# BLDC_driver_sensorless_power.net
KiCad netlist of a schematic drawn in Altium Designer
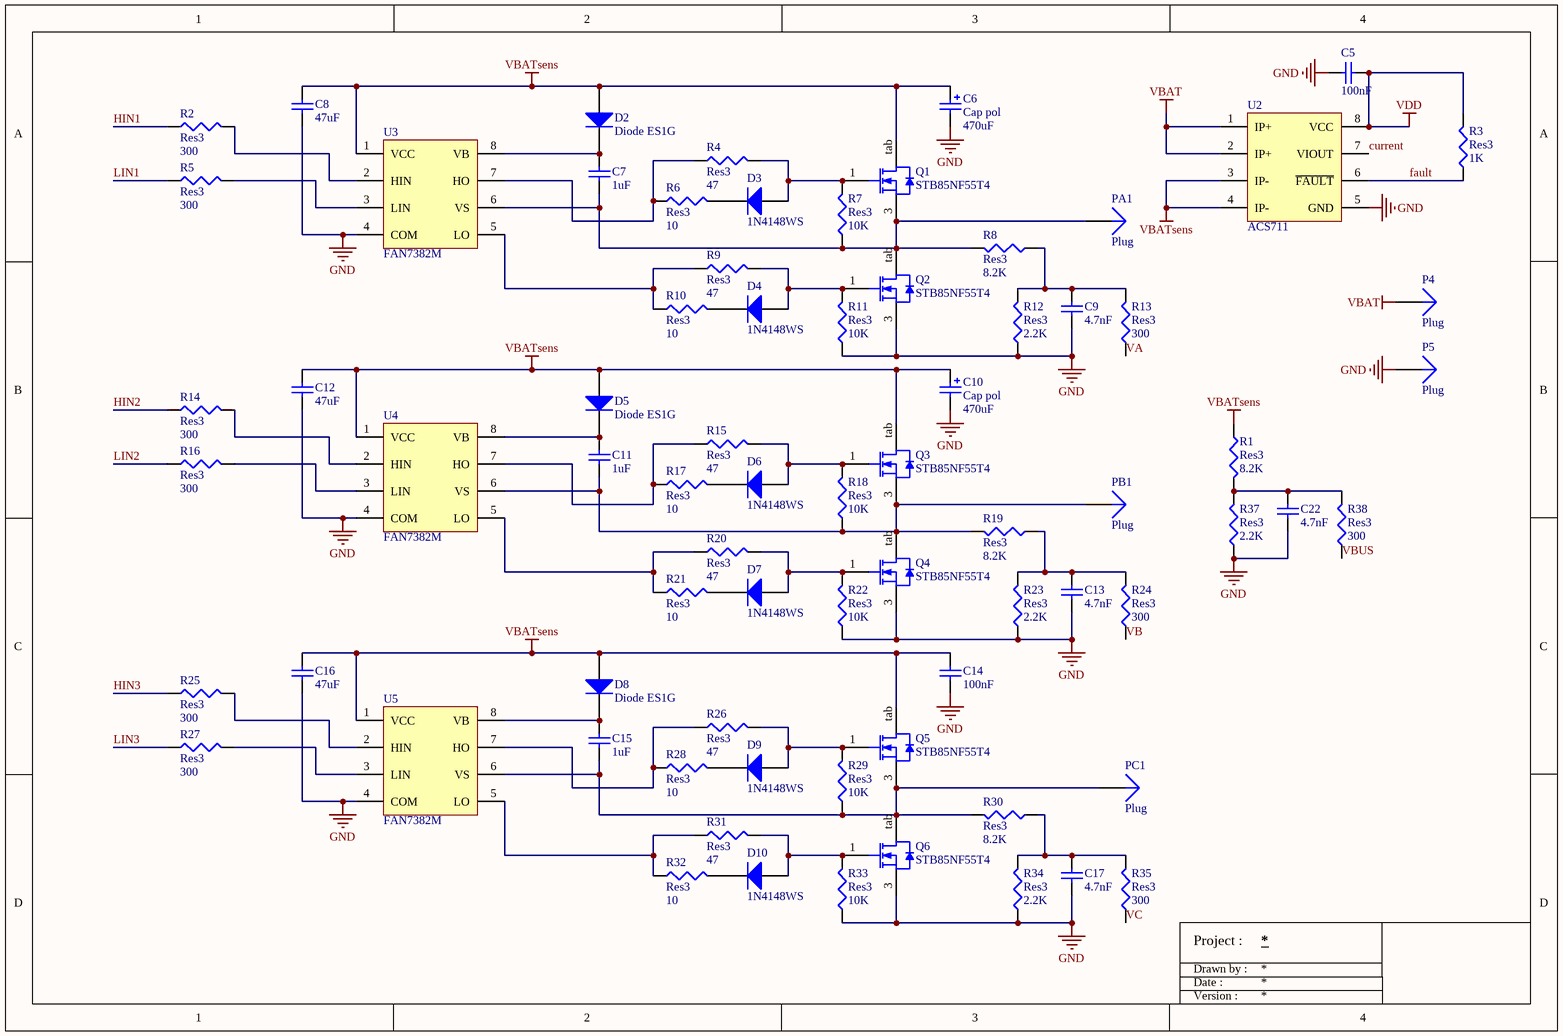
[diagram p0: BLDC_driver_sensorless_power.SchDoc]

(export (version "E")
  (design (tool "Eeschema 10.0.6"))
  (components
    (comp (ref "C5")
      (value "100nF")
      (footprint "1206 capacitor")
      (description "SMD capacitor")
      (fields (field (name "Comment") "Cap SMD"))
      (libsource (lib "Miscellaneous Devices") (part "Cap SMD"))
    )
    (comp (ref "C6")
      (value "Cap pol")
      (footprint "Cap elec 10x16-5 Surface Mount")
      (description "Capa pol through hole")
      (fields (field (name "ALTIUM_VALUE") "470uF"))
      (libsource (lib "Miscellaneous Devices 2") (part "Cap pol"))
    )
    (comp (ref "C7")
      (value "1uF")
      (footprint "1206 capacitor")
      (description "SMD capacitor")
      (fields (field (name "Comment") "Cap SMD"))
      (libsource (lib "Miscellaneous Devices") (part "Cap SMD"))
    )
    (comp (ref "C8")
      (value "47uF")
      (footprint "1206 capacitor")
      (description "SMD capacitor")
      (fields (field (name "Comment") "Cap SMD"))
      (libsource (lib "Miscellaneous Devices") (part "Cap SMD"))
    )
    (comp (ref "C9")
      (value "4.7nF")
      (footprint "1206 capacitor")
      (description "SMD capacitor")
      (fields (field (name "Comment") "Cap SMD"))
      (libsource (lib "Miscellaneous Devices") (part "Cap SMD"))
    )
    (comp (ref "C10")
      (value "Cap pol")
      (footprint "Cap elec 10x16-5 Surface Mount")
      (description "Capa pol through hole")
      (fields (field (name "ALTIUM_VALUE") "470uF"))
      (libsource (lib "Miscellaneous Devices 2") (part "Cap pol"))
    )
    (comp (ref "C11")
      (value "1uF")
      (footprint "1206 capacitor")
      (description "SMD capacitor")
      (fields (field (name "Comment") "Cap SMD"))
      (libsource (lib "Miscellaneous Devices") (part "Cap SMD"))
    )
    (comp (ref "C12")
      (value "47uF")
      (footprint "1206 capacitor")
      (description "SMD capacitor")
      (fields (field (name "Comment") "Cap SMD"))
      (libsource (lib "Miscellaneous Devices") (part "Cap SMD"))
    )
    (comp (ref "C13")
      (value "4.7nF")
      (footprint "1206 capacitor")
      (description "SMD capacitor")
      (fields (field (name "Comment") "Cap SMD"))
      (libsource (lib "Miscellaneous Devices") (part "Cap SMD"))
    )
    (comp (ref "C14")
      (value "100nF")
      (footprint "1206 capacitor")
      (description "SMD capacitor")
      (fields (field (name "Comment") "Cap SMD"))
      (libsource (lib "Miscellaneous Devices") (part "Cap SMD"))
    )
    (comp (ref "C15")
      (value "1uF")
      (footprint "1206 capacitor")
      (description "SMD capacitor")
      (fields (field (name "Comment") "Cap SMD"))
      (libsource (lib "Miscellaneous Devices") (part "Cap SMD"))
    )
    (comp (ref "C16")
      (value "47uF")
      (footprint "1206 capacitor")
      (description "SMD capacitor")
      (fields (field (name "Comment") "Cap SMD"))
      (libsource (lib "Miscellaneous Devices") (part "Cap SMD"))
    )
    (comp (ref "C17")
      (value "4.7nF")
      (footprint "1206 capacitor")
      (description "SMD capacitor")
      (fields (field (name "Comment") "Cap SMD"))
      (libsource (lib "Miscellaneous Devices") (part "Cap SMD"))
    )
    (comp (ref "C22")
      (value "4.7nF")
      (footprint "1206 capacitor")
      (description "SMD capacitor")
      (fields (field (name "Comment") "Cap SMD"))
      (libsource (lib "Miscellaneous Devices") (part "Cap SMD"))
    )
    (comp (ref "D2")
      (value "Diode ES1G")
      (footprint "DO-214AC")
      (description "1.0A SURFACE MOUNT SUPER-FAST RECTIFIER")
      (libsource (lib "Miscellaneous Devices 2") (part "Diode ES1G"))
    )
    (comp (ref "D3")
      (value "1N4148WS")
      (footprint "SOD323")
      (description "Diode commutation")
      (libsource (lib "Miscellaneous Devices 2") (part "1N4148WS"))
    )
    (comp (ref "D4")
      (value "1N4148WS")
      (footprint "SOD323")
      (description "Diode commutation")
      (libsource (lib "Miscellaneous Devices 2") (part "1N4148WS"))
    )
    (comp (ref "D5")
      (value "Diode ES1G")
      (footprint "DO-214AC")
      (description "1.0A SURFACE MOUNT SUPER-FAST RECTIFIER")
      (libsource (lib "Miscellaneous Devices 2") (part "Diode ES1G"))
    )
    (comp (ref "D6")
      (value "1N4148WS")
      (footprint "SOD323")
      (description "Diode commutation")
      (libsource (lib "Miscellaneous Devices 2") (part "1N4148WS"))
    )
    (comp (ref "D7")
      (value "1N4148WS")
      (footprint "SOD323")
      (description "Diode commutation")
      (libsource (lib "Miscellaneous Devices 2") (part "1N4148WS"))
    )
    (comp (ref "D8")
      (value "Diode ES1G")
      (footprint "DO-214AC")
      (description "1.0A SURFACE MOUNT SUPER-FAST RECTIFIER")
      (libsource (lib "Miscellaneous Devices 2") (part "Diode ES1G"))
    )
    (comp (ref "D9")
      (value "1N4148WS")
      (footprint "SOD323")
      (description "Diode commutation")
      (libsource (lib "Miscellaneous Devices 2") (part "1N4148WS"))
    )
    (comp (ref "D10")
      (value "1N4148WS")
      (footprint "SOD323")
      (description "Diode commutation")
      (libsource (lib "Miscellaneous Devices 2") (part "1N4148WS"))
    )
    (comp (ref "P4")
      (value "Plug")
      (footprint "PIN1")
      (fields (field (name "PUBLISHER") "Altium Limited"))
      (libsource (lib "Miscellaneous Connectors") (part "Plug"))
    )
    (comp (ref "P5")
      (value "Plug")
      (footprint "PIN1")
      (fields (field (name "PUBLISHER") "Altium Limited"))
      (libsource (lib "Miscellaneous Connectors") (part "Plug"))
    )
    (comp (ref "PA1")
      (value "Plug")
      (footprint "PIN1")
      (fields (field (name "PUBLISHER") "Altium Limited"))
      (libsource (lib "Miscellaneous Connectors") (part "Plug"))
    )
    (comp (ref "PB1")
      (value "Plug")
      (footprint "PIN1")
      (fields (field (name "PUBLISHER") "Altium Limited"))
      (libsource (lib "Miscellaneous Connectors") (part "Plug"))
    )
    (comp (ref "PC1")
      (value "Plug")
      (footprint "PIN1")
      (fields (field (name "PUBLISHER") "Altium Limited"))
      (libsource (lib "Miscellaneous Connectors") (part "Plug"))
    )
    (comp (ref "Q1")
      (value "STB85NF55T4")
      (footprint "TO-263-2")
      (description "MOSFET Canal-N, 80A 55V")
      (libsource (lib "Miscellaneous Devices 2") (part "STB85NF55T4"))
    )
    (comp (ref "Q2")
      (value "STB85NF55T4")
      (footprint "TO-263-2")
      (description "MOSFET Canal-N, 80A 55V")
      (libsource (lib "Miscellaneous Devices 2") (part "STB85NF55T4"))
    )
    (comp (ref "Q3")
      (value "STB85NF55T4")
      (footprint "TO-263-2")
      (description "MOSFET Canal-N, 80A 55V")
      (libsource (lib "Miscellaneous Devices 2") (part "STB85NF55T4"))
    )
    (comp (ref "Q4")
      (value "STB85NF55T4")
      (footprint "TO-263-2")
      (description "MOSFET Canal-N, 80A 55V")
      (libsource (lib "Miscellaneous Devices 2") (part "STB85NF55T4"))
    )
    (comp (ref "Q5")
      (value "STB85NF55T4")
      (footprint "TO-263-2")
      (description "MOSFET Canal-N, 80A 55V")
      (libsource (lib "Miscellaneous Devices 2") (part "STB85NF55T4"))
    )
    (comp (ref "Q6")
      (value "STB85NF55T4")
      (footprint "TO-263-2")
      (description "MOSFET Canal-N, 80A 55V")
      (libsource (lib "Miscellaneous Devices 2") (part "STB85NF55T4"))
    )
    (comp (ref "R1")
      (value "Res3")
      (footprint "1206 resistor")
      (description "Resistor")
      (fields (field (name "ALTIUM_VALUE") "8.2K") (field (name "PUBLISHER") "Altium Limited"))
      (libsource (lib "Miscellaneous Devices") (part "Res3"))
    )
    (comp (ref "R2")
      (value "Res3")
      (footprint "1206 resistor")
      (description "Resistor")
      (fields (field (name "ALTIUM_VALUE") "300") (field (name "PUBLISHER") "Altium Limited"))
      (libsource (lib "Miscellaneous Devices") (part "Res3"))
    )
    (comp (ref "R3")
      (value "Res3")
      (footprint "1206 resistor")
      (description "Resistor")
      (fields (field (name "ALTIUM_VALUE") "1K") (field (name "PUBLISHER") "Altium Limited"))
      (libsource (lib "Miscellaneous Devices") (part "Res3"))
    )
    (comp (ref "R4")
      (value "Res3")
      (footprint "1206 resistor")
      (description "Resistor")
      (fields (field (name "ALTIUM_VALUE") "47") (field (name "PUBLISHER") "Altium Limited"))
      (libsource (lib "Miscellaneous Devices") (part "Res3"))
    )
    (comp (ref "R5")
      (value "Res3")
      (footprint "1206 resistor")
      (description "Resistor")
      (fields (field (name "ALTIUM_VALUE") "300") (field (name "PUBLISHER") "Altium Limited"))
      (libsource (lib "Miscellaneous Devices") (part "Res3"))
    )
    (comp (ref "R6")
      (value "Res3")
      (footprint "1206 resistor")
      (description "Resistor")
      (fields (field (name "ALTIUM_VALUE") "10") (field (name "PUBLISHER") "Altium Limited"))
      (libsource (lib "Miscellaneous Devices") (part "Res3"))
    )
    (comp (ref "R7")
      (value "Res3")
      (footprint "1206 resistor")
      (description "Resistor")
      (fields (field (name "ALTIUM_VALUE") "10K") (field (name "PUBLISHER") "Altium Limited"))
      (libsource (lib "Miscellaneous Devices") (part "Res3"))
    )
    (comp (ref "R8")
      (value "Res3")
      (footprint "1206 resistor")
      (description "Resistor")
      (fields (field (name "ALTIUM_VALUE") "8.2K") (field (name "PUBLISHER") "Altium Limited"))
      (libsource (lib "Miscellaneous Devices") (part "Res3"))
    )
    (comp (ref "R9")
      (value "Res3")
      (footprint "1206 resistor")
      (description "Resistor")
      (fields (field (name "ALTIUM_VALUE") "47") (field (name "PUBLISHER") "Altium Limited"))
      (libsource (lib "Miscellaneous Devices") (part "Res3"))
    )
    (comp (ref "R10")
      (value "Res3")
      (footprint "1206 resistor")
      (description "Resistor")
      (fields (field (name "ALTIUM_VALUE") "10") (field (name "PUBLISHER") "Altium Limited"))
      (libsource (lib "Miscellaneous Devices") (part "Res3"))
    )
    (comp (ref "R11")
      (value "Res3")
      (footprint "1206 resistor")
      (description "Resistor")
      (fields (field (name "ALTIUM_VALUE") "10K") (field (name "PUBLISHER") "Altium Limited"))
      (libsource (lib "Miscellaneous Devices") (part "Res3"))
    )
    (comp (ref "R12")
      (value "Res3")
      (footprint "1206 resistor")
      (description "Resistor")
      (fields (field (name "ALTIUM_VALUE") "2.2K") (field (name "PUBLISHER") "Altium Limited"))
      (libsource (lib "Miscellaneous Devices") (part "Res3"))
    )
    (comp (ref "R13")
      (value "Res3")
      (footprint "1206 resistor")
      (description "Resistor")
      (fields (field (name "ALTIUM_VALUE") "300") (field (name "PUBLISHER") "Altium Limited"))
      (libsource (lib "Miscellaneous Devices") (part "Res3"))
    )
    (comp (ref "R14")
      (value "Res3")
      (footprint "1206 resistor")
      (description "Resistor")
      (fields (field (name "ALTIUM_VALUE") "300") (field (name "PUBLISHER") "Altium Limited"))
      (libsource (lib "Miscellaneous Devices") (part "Res3"))
    )
    (comp (ref "R15")
      (value "Res3")
      (footprint "1206 resistor")
      (description "Resistor")
      (fields (field (name "ALTIUM_VALUE") "47") (field (name "PUBLISHER") "Altium Limited"))
      (libsource (lib "Miscellaneous Devices") (part "Res3"))
    )
    (comp (ref "R16")
      (value "Res3")
      (footprint "1206 resistor")
      (description "Resistor")
      (fields (field (name "ALTIUM_VALUE") "300") (field (name "PUBLISHER") "Altium Limited"))
      (libsource (lib "Miscellaneous Devices") (part "Res3"))
    )
    (comp (ref "R17")
      (value "Res3")
      (footprint "1206 resistor")
      (description "Resistor")
      (fields (field (name "ALTIUM_VALUE") "10") (field (name "PUBLISHER") "Altium Limited"))
      (libsource (lib "Miscellaneous Devices") (part "Res3"))
    )
    (comp (ref "R18")
      (value "Res3")
      (footprint "1206 resistor")
      (description "Resistor")
      (fields (field (name "ALTIUM_VALUE") "10K") (field (name "PUBLISHER") "Altium Limited"))
      (libsource (lib "Miscellaneous Devices") (part "Res3"))
    )
    (comp (ref "R19")
      (value "Res3")
      (footprint "1206 resistor")
      (description "Resistor")
      (fields (field (name "ALTIUM_VALUE") "8.2K") (field (name "PUBLISHER") "Altium Limited"))
      (libsource (lib "Miscellaneous Devices") (part "Res3"))
    )
    (comp (ref "R20")
      (value "Res3")
      (footprint "1206 resistor")
      (description "Resistor")
      (fields (field (name "ALTIUM_VALUE") "47") (field (name "PUBLISHER") "Altium Limited"))
      (libsource (lib "Miscellaneous Devices") (part "Res3"))
    )
    (comp (ref "R21")
      (value "Res3")
      (footprint "1206 resistor")
      (description "Resistor")
      (fields (field (name "ALTIUM_VALUE") "10") (field (name "PUBLISHER") "Altium Limited"))
      (libsource (lib "Miscellaneous Devices") (part "Res3"))
    )
    (comp (ref "R22")
      (value "Res3")
      (footprint "1206 resistor")
      (description "Resistor")
      (fields (field (name "ALTIUM_VALUE") "10K") (field (name "PUBLISHER") "Altium Limited"))
      (libsource (lib "Miscellaneous Devices") (part "Res3"))
    )
    (comp (ref "R23")
      (value "Res3")
      (footprint "1206 resistor")
      (description "Resistor")
      (fields (field (name "ALTIUM_VALUE") "2.2K") (field (name "PUBLISHER") "Altium Limited"))
      (libsource (lib "Miscellaneous Devices") (part "Res3"))
    )
    (comp (ref "R24")
      (value "Res3")
      (footprint "1206 resistor")
      (description "Resistor")
      (fields (field (name "ALTIUM_VALUE") "300") (field (name "PUBLISHER") "Altium Limited"))
      (libsource (lib "Miscellaneous Devices") (part "Res3"))
    )
    (comp (ref "R25")
      (value "Res3")
      (footprint "1206 resistor")
      (description "Resistor")
      (fields (field (name "ALTIUM_VALUE") "300") (field (name "PUBLISHER") "Altium Limited"))
      (libsource (lib "Miscellaneous Devices") (part "Res3"))
    )
    (comp (ref "R26")
      (value "Res3")
      (footprint "1206 resistor")
      (description "Resistor")
      (fields (field (name "ALTIUM_VALUE") "47") (field (name "PUBLISHER") "Altium Limited"))
      (libsource (lib "Miscellaneous Devices") (part "Res3"))
    )
    (comp (ref "R27")
      (value "Res3")
      (footprint "1206 resistor")
      (description "Resistor")
      (fields (field (name "ALTIUM_VALUE") "300") (field (name "PUBLISHER") "Altium Limited"))
      (libsource (lib "Miscellaneous Devices") (part "Res3"))
    )
    (comp (ref "R28")
      (value "Res3")
      (footprint "1206 resistor")
      (description "Resistor")
      (fields (field (name "ALTIUM_VALUE") "10") (field (name "PUBLISHER") "Altium Limited"))
      (libsource (lib "Miscellaneous Devices") (part "Res3"))
    )
    (comp (ref "R29")
      (value "Res3")
      (footprint "1206 resistor")
      (description "Resistor")
      (fields (field (name "ALTIUM_VALUE") "10K") (field (name "PUBLISHER") "Altium Limited"))
      (libsource (lib "Miscellaneous Devices") (part "Res3"))
    )
    (comp (ref "R30")
      (value "Res3")
      (footprint "1206 resistor")
      (description "Resistor")
      (fields (field (name "ALTIUM_VALUE") "8.2K") (field (name "PUBLISHER") "Altium Limited"))
      (libsource (lib "Miscellaneous Devices") (part "Res3"))
    )
    (comp (ref "R31")
      (value "Res3")
      (footprint "1206 resistor")
      (description "Resistor")
      (fields (field (name "ALTIUM_VALUE") "47") (field (name "PUBLISHER") "Altium Limited"))
      (libsource (lib "Miscellaneous Devices") (part "Res3"))
    )
    (comp (ref "R32")
      (value "Res3")
      (footprint "1206 resistor")
      (description "Resistor")
      (fields (field (name "ALTIUM_VALUE") "10") (field (name "PUBLISHER") "Altium Limited"))
      (libsource (lib "Miscellaneous Devices") (part "Res3"))
    )
    (comp (ref "R33")
      (value "Res3")
      (footprint "1206 resistor")
      (description "Resistor")
      (fields (field (name "ALTIUM_VALUE") "10K") (field (name "PUBLISHER") "Altium Limited"))
      (libsource (lib "Miscellaneous Devices") (part "Res3"))
    )
    (comp (ref "R34")
      (value "Res3")
      (footprint "1206 resistor")
      (description "Resistor")
      (fields (field (name "ALTIUM_VALUE") "2.2K") (field (name "PUBLISHER") "Altium Limited"))
      (libsource (lib "Miscellaneous Devices") (part "Res3"))
    )
    (comp (ref "R35")
      (value "Res3")
      (footprint "1206 resistor")
      (description "Resistor")
      (fields (field (name "ALTIUM_VALUE") "300") (field (name "PUBLISHER") "Altium Limited"))
      (libsource (lib "Miscellaneous Devices") (part "Res3"))
    )
    (comp (ref "R37")
      (value "Res3")
      (footprint "1206 resistor")
      (description "Resistor")
      (fields (field (name "ALTIUM_VALUE") "2.2K") (field (name "PUBLISHER") "Altium Limited"))
      (libsource (lib "Miscellaneous Devices") (part "Res3"))
    )
    (comp (ref "R38")
      (value "Res3")
      (footprint "1206 resistor")
      (description "Resistor")
      (fields (field (name "ALTIUM_VALUE") "300") (field (name "PUBLISHER") "Altium Limited"))
      (libsource (lib "Miscellaneous Devices") (part "Res3"))
    )
    (comp (ref "U2")
      (value "ACS711")
      (footprint "SOIC8")
      (description "+/-12A HALL EFFECT CURRENT SENSOR")
      (libsource (lib "Miscellaneous Devices 2") (part "ACS711"))
    )
    (comp (ref "U3")
      (value "FAN7382M")
      (footprint "SOIC8")
      (description "High and Low Side Gate Driver")
      (libsource (lib "Miscellaneous Devices 2") (part "FAN7382M"))
    )
    (comp (ref "U4")
      (value "FAN7382M")
      (footprint "SOIC8")
      (description "High and Low Side Gate Driver")
      (libsource (lib "Miscellaneous Devices 2") (part "FAN7382M"))
    )
    (comp (ref "U5")
      (value "FAN7382M")
      (footprint "SOIC8")
      (description "High and Low Side Gate Driver")
      (libsource (lib "Miscellaneous Devices 2") (part "FAN7382M"))
    )
  )
  (nets
    (net (code "1") (name "/HIN1") (class "Default")
      (node (ref "R2") (pin "1") (pinfunction "1_1") (pintype "passive"))
    )
    (net (code "2") (name "/HIN2") (class "Default")
      (node (ref "R14") (pin "1") (pinfunction "1_1") (pintype "passive"))
    )
    (net (code "3") (name "/HIN3") (class "Default")
      (node (ref "R25") (pin "1") (pinfunction "1_1") (pintype "passive"))
    )
    (net (code "4") (name "/LIN1") (class "Default")
      (node (ref "R5") (pin "1") (pinfunction "1_1") (pintype "passive"))
    )
    (net (code "5") (name "/LIN2") (class "Default")
      (node (ref "R16") (pin "1") (pinfunction "1_1") (pintype "passive"))
    )
    (net (code "6") (name "/LIN3") (class "Default")
      (node (ref "R27") (pin "1") (pinfunction "1_1") (pintype "passive"))
    )
    (net (code "7") (name "/VA") (class "Default")
      (node (ref "R13") (pin "1") (pinfunction "1_1") (pintype "passive"))
    )
    (net (code "8") (name "/VB") (class "Default")
      (node (ref "R24") (pin "1") (pinfunction "1_1") (pintype "passive"))
    )
    (net (code "9") (name "/VBUS") (class "Default")
      (node (ref "R38") (pin "1") (pinfunction "1_1") (pintype "passive"))
    )
    (net (code "10") (name "/VC") (class "Default")
      (node (ref "R35") (pin "1") (pinfunction "1_1") (pintype "passive"))
    )
    (net (code "11") (name "/current") (class "Default")
      (node (ref "U2") (pin "7") (pinfunction "VIOUT_7") (pintype "passive"))
    )
    (net (code "12") (name "/fault") (class "Default")
      (node (ref "R3") (pin "1") (pinfunction "1_1") (pintype "passive"))
      (node (ref "U2") (pin "6") (pinfunction "~{FAULT}_6") (pintype "passive"))
    )
    (net (code "13") (name "GND") (class "Default")
      (node (ref "C10") (pin "2") (pinfunction "2_2") (pintype "passive"))
      (node (ref "C12") (pin "1") (pinfunction "1_1") (pintype "passive"))
      (node (ref "C13") (pin "2") (pinfunction "2_2") (pintype "passive"))
      (node (ref "C14") (pin "2") (pinfunction "2_2") (pintype "passive"))
      (node (ref "C16") (pin "1") (pinfunction "1_1") (pintype "passive"))
      (node (ref "C17") (pin "2") (pinfunction "2_2") (pintype "passive"))
      (node (ref "C22") (pin "2") (pinfunction "2_2") (pintype "passive"))
      (node (ref "C5") (pin "2") (pinfunction "2_2") (pintype "passive"))
      (node (ref "C6") (pin "2") (pinfunction "2_2") (pintype "passive"))
      (node (ref "C8") (pin "1") (pinfunction "1_1") (pintype "passive"))
      (node (ref "C9") (pin "2") (pinfunction "2_2") (pintype "passive"))
      (node (ref "P5") (pin "1") (pinfunction "1_1") (pintype "passive"))
      (node (ref "Q2") (pin "3") (pinfunction "S_3") (pintype "passive"))
      (node (ref "Q4") (pin "3") (pinfunction "S_3") (pintype "passive"))
      (node (ref "Q6") (pin "3") (pinfunction "S_3") (pintype "passive"))
      (node (ref "R11") (pin "1") (pinfunction "1_1") (pintype "passive"))
      (node (ref "R12") (pin "1") (pinfunction "1_1") (pintype "passive"))
      (node (ref "R22") (pin "1") (pinfunction "1_1") (pintype "passive"))
      (node (ref "R23") (pin "1") (pinfunction "1_1") (pintype "passive"))
      (node (ref "R33") (pin "1") (pinfunction "1_1") (pintype "passive"))
      (node (ref "R34") (pin "1") (pinfunction "1_1") (pintype "passive"))
      (node (ref "R37") (pin "1") (pinfunction "1_1") (pintype "passive"))
      (node (ref "U2") (pin "5") (pinfunction "GND_5") (pintype "passive"))
      (node (ref "U3") (pin "4") (pinfunction "COM_4") (pintype "passive"))
      (node (ref "U4") (pin "4") (pinfunction "COM_4") (pintype "passive"))
      (node (ref "U5") (pin "4") (pinfunction "COM_4") (pintype "passive"))
    )
    (net (code "14") (name "Net-(C9-Pad1)") (class "Default")
      (node (ref "C9") (pin "1") (pinfunction "1_1") (pintype "passive"))
      (node (ref "R12") (pin "2") (pinfunction "2_2") (pintype "passive"))
      (node (ref "R13") (pin "2") (pinfunction "2_2") (pintype "passive"))
      (node (ref "R8") (pin "1") (pinfunction "1_1") (pintype "passive"))
    )
    (net (code "15") (name "Net-(C13-Pad1)") (class "Default")
      (node (ref "C13") (pin "1") (pinfunction "1_1") (pintype "passive"))
      (node (ref "R19") (pin "1") (pinfunction "1_1") (pintype "passive"))
      (node (ref "R23") (pin "2") (pinfunction "2_2") (pintype "passive"))
      (node (ref "R24") (pin "2") (pinfunction "2_2") (pintype "passive"))
    )
    (net (code "16") (name "Net-(C17-Pad1)") (class "Default")
      (node (ref "C17") (pin "1") (pinfunction "1_1") (pintype "passive"))
      (node (ref "R30") (pin "1") (pinfunction "1_1") (pintype "passive"))
      (node (ref "R34") (pin "2") (pinfunction "2_2") (pintype "passive"))
      (node (ref "R35") (pin "2") (pinfunction "2_2") (pintype "passive"))
    )
    (net (code "17") (name "Net-(C22-Pad1)") (class "Default")
      (node (ref "C22") (pin "1") (pinfunction "1_1") (pintype "passive"))
      (node (ref "R1") (pin "2") (pinfunction "2_2") (pintype "passive"))
      (node (ref "R37") (pin "2") (pinfunction "2_2") (pintype "passive"))
      (node (ref "R38") (pin "2") (pinfunction "2_2") (pintype "passive"))
    )
    (net (code "18") (name "Net-(D3-A)") (class "Default")
      (node (ref "D3") (pin "1") (pinfunction "A_1") (pintype "passive"))
      (node (ref "Q1") (pin "1") (pinfunction "G_1") (pintype "passive"))
      (node (ref "R4") (pin "2") (pinfunction "2_2") (pintype "passive"))
      (node (ref "R7") (pin "2") (pinfunction "2_2") (pintype "passive"))
    )
    (net (code "19") (name "Net-(D3-K)") (class "Default")
      (node (ref "D3") (pin "2") (pinfunction "K_2") (pintype "passive"))
      (node (ref "R6") (pin "2") (pinfunction "2_2") (pintype "passive"))
    )
    (net (code "20") (name "Net-(D4-A)") (class "Default")
      (node (ref "D4") (pin "1") (pinfunction "A_1") (pintype "passive"))
      (node (ref "Q2") (pin "1") (pinfunction "G_1") (pintype "passive"))
      (node (ref "R11") (pin "2") (pinfunction "2_2") (pintype "passive"))
      (node (ref "R9") (pin "2") (pinfunction "2_2") (pintype "passive"))
    )
    (net (code "21") (name "Net-(D4-K)") (class "Default")
      (node (ref "D4") (pin "2") (pinfunction "K_2") (pintype "passive"))
      (node (ref "R10") (pin "2") (pinfunction "2_2") (pintype "passive"))
    )
    (net (code "22") (name "Net-(D6-A)") (class "Default")
      (node (ref "D6") (pin "1") (pinfunction "A_1") (pintype "passive"))
      (node (ref "Q3") (pin "1") (pinfunction "G_1") (pintype "passive"))
      (node (ref "R15") (pin "2") (pinfunction "2_2") (pintype "passive"))
      (node (ref "R18") (pin "2") (pinfunction "2_2") (pintype "passive"))
    )
    (net (code "23") (name "Net-(D6-K)") (class "Default")
      (node (ref "D6") (pin "2") (pinfunction "K_2") (pintype "passive"))
      (node (ref "R17") (pin "2") (pinfunction "2_2") (pintype "passive"))
    )
    (net (code "24") (name "Net-(D7-A)") (class "Default")
      (node (ref "D7") (pin "1") (pinfunction "A_1") (pintype "passive"))
      (node (ref "Q4") (pin "1") (pinfunction "G_1") (pintype "passive"))
      (node (ref "R20") (pin "2") (pinfunction "2_2") (pintype "passive"))
      (node (ref "R22") (pin "2") (pinfunction "2_2") (pintype "passive"))
    )
    (net (code "25") (name "Net-(D7-K)") (class "Default")
      (node (ref "D7") (pin "2") (pinfunction "K_2") (pintype "passive"))
      (node (ref "R21") (pin "2") (pinfunction "2_2") (pintype "passive"))
    )
    (net (code "26") (name "Net-(D9-A)") (class "Default")
      (node (ref "D9") (pin "1") (pinfunction "A_1") (pintype "passive"))
      (node (ref "Q5") (pin "1") (pinfunction "G_1") (pintype "passive"))
      (node (ref "R26") (pin "2") (pinfunction "2_2") (pintype "passive"))
      (node (ref "R29") (pin "2") (pinfunction "2_2") (pintype "passive"))
    )
    (net (code "27") (name "Net-(D9-K)") (class "Default")
      (node (ref "D9") (pin "2") (pinfunction "K_2") (pintype "passive"))
      (node (ref "R28") (pin "2") (pinfunction "2_2") (pintype "passive"))
    )
    (net (code "28") (name "Net-(D10-A)") (class "Default")
      (node (ref "D10") (pin "1") (pinfunction "A_1") (pintype "passive"))
      (node (ref "Q6") (pin "1") (pinfunction "G_1") (pintype "passive"))
      (node (ref "R31") (pin "2") (pinfunction "2_2") (pintype "passive"))
      (node (ref "R33") (pin "2") (pinfunction "2_2") (pintype "passive"))
    )
    (net (code "29") (name "Net-(D10-K)") (class "Default")
      (node (ref "D10") (pin "2") (pinfunction "K_2") (pintype "passive"))
      (node (ref "R32") (pin "2") (pinfunction "2_2") (pintype "passive"))
    )
    (net (code "30") (name "Net-(Q1-S)") (class "Default")
      (node (ref "C7") (pin "2") (pinfunction "2_2") (pintype "passive"))
      (node (ref "PA1") (pin "1") (pinfunction "1_1") (pintype "passive"))
      (node (ref "Q1") (pin "3") (pinfunction "S_3") (pintype "passive"))
      (node (ref "Q2") (pin "tab") (pinfunction "D_tab") (pintype "passive"))
      (node (ref "R7") (pin "1") (pinfunction "1_1") (pintype "passive"))
      (node (ref "R8") (pin "2") (pinfunction "2_2") (pintype "passive"))
      (node (ref "U3") (pin "6") (pinfunction "VS_6") (pintype "passive"))
    )
    (net (code "31") (name "Net-(Q3-S)") (class "Default")
      (node (ref "C11") (pin "2") (pinfunction "2_2") (pintype "passive"))
      (node (ref "PB1") (pin "1") (pinfunction "1_1") (pintype "passive"))
      (node (ref "Q3") (pin "3") (pinfunction "S_3") (pintype "passive"))
      (node (ref "Q4") (pin "tab") (pinfunction "D_tab") (pintype "passive"))
      (node (ref "R18") (pin "1") (pinfunction "1_1") (pintype "passive"))
      (node (ref "R19") (pin "2") (pinfunction "2_2") (pintype "passive"))
      (node (ref "U4") (pin "6") (pinfunction "VS_6") (pintype "passive"))
    )
    (net (code "32") (name "Net-(Q5-S)") (class "Default")
      (node (ref "C15") (pin "2") (pinfunction "2_2") (pintype "passive"))
      (node (ref "PC1") (pin "1") (pinfunction "1_1") (pintype "passive"))
      (node (ref "Q5") (pin "3") (pinfunction "S_3") (pintype "passive"))
      (node (ref "Q6") (pin "tab") (pinfunction "D_tab") (pintype "passive"))
      (node (ref "R29") (pin "1") (pinfunction "1_1") (pintype "passive"))
      (node (ref "R30") (pin "2") (pinfunction "2_2") (pintype "passive"))
      (node (ref "U5") (pin "6") (pinfunction "VS_6") (pintype "passive"))
    )
    (net (code "33") (name "Net-(U3-HIN)") (class "Default")
      (node (ref "R2") (pin "2") (pinfunction "2_2") (pintype "passive"))
      (node (ref "U3") (pin "2") (pinfunction "HIN_2") (pintype "passive"))
    )
    (net (code "34") (name "Net-(U3-HO)") (class "Default")
      (node (ref "R4") (pin "1") (pinfunction "1_1") (pintype "passive"))
      (node (ref "R6") (pin "1") (pinfunction "1_1") (pintype "passive"))
      (node (ref "U3") (pin "7") (pinfunction "HO_7") (pintype "passive"))
    )
    (net (code "35") (name "Net-(U3-LIN)") (class "Default")
      (node (ref "R5") (pin "2") (pinfunction "2_2") (pintype "passive"))
      (node (ref "U3") (pin "3") (pinfunction "LIN_3") (pintype "passive"))
    )
    (net (code "36") (name "Net-(U3-LO)") (class "Default")
      (node (ref "R10") (pin "1") (pinfunction "1_1") (pintype "passive"))
      (node (ref "R9") (pin "1") (pinfunction "1_1") (pintype "passive"))
      (node (ref "U3") (pin "5") (pinfunction "LO_5") (pintype "passive"))
    )
    (net (code "37") (name "Net-(U3-VB)") (class "Default")
      (node (ref "C7") (pin "1") (pinfunction "1_1") (pintype "passive"))
      (node (ref "D2") (pin "K") (pinfunction "K_K") (pintype "passive"))
      (node (ref "U3") (pin "8") (pinfunction "VB_8") (pintype "passive"))
    )
    (net (code "38") (name "Net-(U4-HIN)") (class "Default")
      (node (ref "R14") (pin "2") (pinfunction "2_2") (pintype "passive"))
      (node (ref "U4") (pin "2") (pinfunction "HIN_2") (pintype "passive"))
    )
    (net (code "39") (name "Net-(U4-HO)") (class "Default")
      (node (ref "R15") (pin "1") (pinfunction "1_1") (pintype "passive"))
      (node (ref "R17") (pin "1") (pinfunction "1_1") (pintype "passive"))
      (node (ref "U4") (pin "7") (pinfunction "HO_7") (pintype "passive"))
    )
    (net (code "40") (name "Net-(U4-LIN)") (class "Default")
      (node (ref "R16") (pin "2") (pinfunction "2_2") (pintype "passive"))
      (node (ref "U4") (pin "3") (pinfunction "LIN_3") (pintype "passive"))
    )
    (net (code "41") (name "Net-(U4-LO)") (class "Default")
      (node (ref "R20") (pin "1") (pinfunction "1_1") (pintype "passive"))
      (node (ref "R21") (pin "1") (pinfunction "1_1") (pintype "passive"))
      (node (ref "U4") (pin "5") (pinfunction "LO_5") (pintype "passive"))
    )
    (net (code "42") (name "Net-(U4-VB)") (class "Default")
      (node (ref "C11") (pin "1") (pinfunction "1_1") (pintype "passive"))
      (node (ref "D5") (pin "K") (pinfunction "K_K") (pintype "passive"))
      (node (ref "U4") (pin "8") (pinfunction "VB_8") (pintype "passive"))
    )
    (net (code "43") (name "Net-(U5-HIN)") (class "Default")
      (node (ref "R25") (pin "2") (pinfunction "2_2") (pintype "passive"))
      (node (ref "U5") (pin "2") (pinfunction "HIN_2") (pintype "passive"))
    )
    (net (code "44") (name "Net-(U5-HO)") (class "Default")
      (node (ref "R26") (pin "1") (pinfunction "1_1") (pintype "passive"))
      (node (ref "R28") (pin "1") (pinfunction "1_1") (pintype "passive"))
      (node (ref "U5") (pin "7") (pinfunction "HO_7") (pintype "passive"))
    )
    (net (code "45") (name "Net-(U5-LIN)") (class "Default")
      (node (ref "R27") (pin "2") (pinfunction "2_2") (pintype "passive"))
      (node (ref "U5") (pin "3") (pinfunction "LIN_3") (pintype "passive"))
    )
    (net (code "46") (name "Net-(U5-LO)") (class "Default")
      (node (ref "R31") (pin "1") (pinfunction "1_1") (pintype "passive"))
      (node (ref "R32") (pin "1") (pinfunction "1_1") (pintype "passive"))
      (node (ref "U5") (pin "5") (pinfunction "LO_5") (pintype "passive"))
    )
    (net (code "47") (name "Net-(U5-VB)") (class "Default")
      (node (ref "C15") (pin "1") (pinfunction "1_1") (pintype "passive"))
      (node (ref "D8") (pin "K") (pinfunction "K_K") (pintype "passive"))
      (node (ref "U5") (pin "8") (pinfunction "VB_8") (pintype "passive"))
    )
    (net (code "48") (name "VBAT") (class "Default")
      (node (ref "P4") (pin "1") (pinfunction "1_1") (pintype "passive"))
      (node (ref "U2") (pin "1") (pinfunction "IP+_1") (pintype "passive"))
      (node (ref "U2") (pin "2") (pinfunction "IP+_2") (pintype "passive"))
    )
    (net (code "49") (name "VBATsens") (class "Default")
      (node (ref "C10") (pin "1") (pinfunction "1_1") (pintype "passive"))
      (node (ref "C12") (pin "2") (pinfunction "2_2") (pintype "passive"))
      (node (ref "C14") (pin "1") (pinfunction "1_1") (pintype "passive"))
      (node (ref "C16") (pin "2") (pinfunction "2_2") (pintype "passive"))
      (node (ref "C6") (pin "1") (pinfunction "1_1") (pintype "passive"))
      (node (ref "C8") (pin "2") (pinfunction "2_2") (pintype "passive"))
      (node (ref "D2") (pin "A") (pinfunction "A_A") (pintype "passive"))
      (node (ref "D5") (pin "A") (pinfunction "A_A") (pintype "passive"))
      (node (ref "D8") (pin "A") (pinfunction "A_A") (pintype "passive"))
      (node (ref "Q1") (pin "tab") (pinfunction "D_tab") (pintype "passive"))
      (node (ref "Q3") (pin "tab") (pinfunction "D_tab") (pintype "passive"))
      (node (ref "Q5") (pin "tab") (pinfunction "D_tab") (pintype "passive"))
      (node (ref "R1") (pin "1") (pinfunction "1_1") (pintype "passive"))
      (node (ref "U2") (pin "3") (pinfunction "IP-_3") (pintype "passive"))
      (node (ref "U2") (pin "4") (pinfunction "IP-_4") (pintype "passive"))
      (node (ref "U3") (pin "1") (pinfunction "VCC_1") (pintype "passive"))
      (node (ref "U4") (pin "1") (pinfunction "VCC_1") (pintype "passive"))
      (node (ref "U5") (pin "1") (pinfunction "VCC_1") (pintype "passive"))
    )
    (net (code "50") (name "VDD") (class "Default")
      (node (ref "C5") (pin "1") (pinfunction "1_1") (pintype "passive"))
      (node (ref "R3") (pin "2") (pinfunction "2_2") (pintype "passive"))
      (node (ref "U2") (pin "8") (pinfunction "VCC_8") (pintype "passive"))
    )
  )
)
